# ESP32_BLDC_Motor_Driver.net
KiCad netlist of a schematic drawn in EAGLE
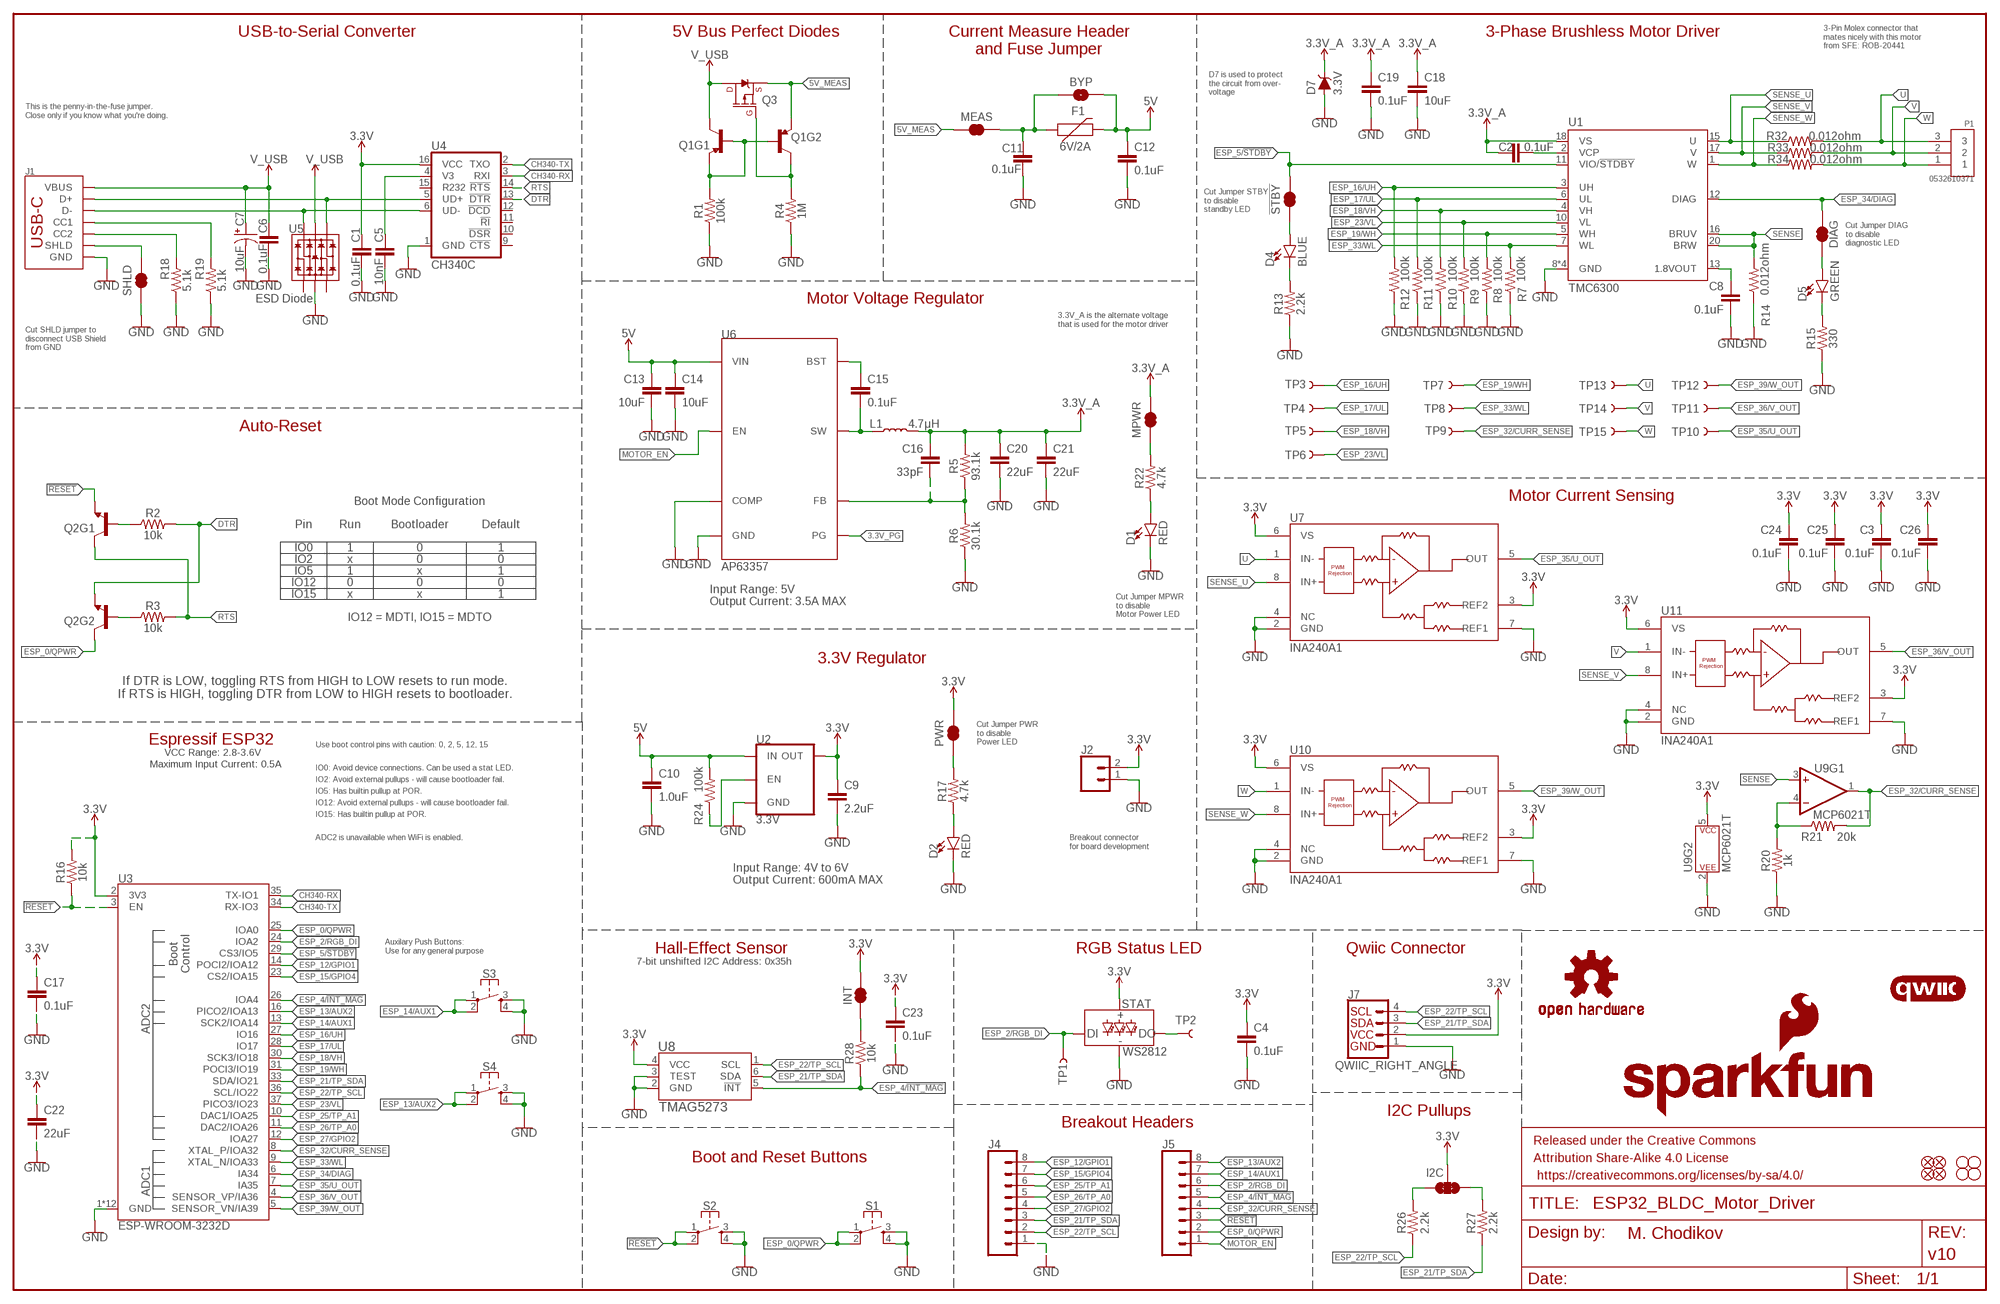
[diagram p0: schematic, sheet 1]

(export (version "E")
  (design (tool "Eeschema 10.0.6"))
  (components
    (comp (ref "!STBY")
      (value "JUMPER-SMT_2_NC_TRACE_SILK")
      (footprint "eagle-import:SMT-JUMPER_2_NC_TRACE_SILK")
      (fields (field (name "SPICEPREFIX") "B"))
      (libsource (lib "eagle-import") (part "JUMPER-SMT_2_NC_TRACE_SILK"))
    )
    (comp (ref "BYP")
      (value "JUMPER-SMT_2_NO_SILK")
      (footprint "eagle-import:SMT-JUMPER_2_NO_SILK")
      (libsource (lib "eagle-import") (part "JUMPER-SMT_2_NO_SILK"))
    )
    (comp (ref "C1")
      (value "0.1uF")
      (footprint "eagle-import:0603")
      (libsource (lib "eagle-import") (part "0.1UF-0603-25V-10%-X7R-WE"))
    )
    (comp (ref "C2")
      (value "0.1uF")
      (footprint "eagle-import:0603")
      (libsource (lib "eagle-import") (part "0.1UF-0603-25V-10%-X7R-WE"))
    )
    (comp (ref "C3")
      (value "0.1uF")
      (footprint "eagle-import:0603")
      (libsource (lib "eagle-import") (part "0.1UF-0603-25V-5%"))
    )
    (comp (ref "C4")
      (value "0.1uF")
      (footprint "eagle-import:0603")
      (libsource (lib "eagle-import") (part "0.1UF-0603-25V-10%-X7R-WE"))
    )
    (comp (ref "C5")
      (value "10nF")
      (footprint "eagle-import:0603")
      (libsource (lib "eagle-import") (part "10NF-0603-50V-10%"))
    )
    (comp (ref "C6")
      (value "0.1uF")
      (footprint "eagle-import:0603")
      (libsource (lib "eagle-import") (part "0.1UF-0603-25V-(+80/-20%)"))
    )
    (comp (ref "C7")
      (value "10uF")
      (footprint "eagle-import:0603-POLAR")
      (libsource (lib "eagle-import") (part "10UF-POLAR-0603-6.3V-20%(TANT)"))
    )
    (comp (ref "C8")
      (value "0.1uF")
      (footprint "eagle-import:0603")
      (libsource (lib "eagle-import") (part "0.1UF-0603-25V-10%-X7R-WE"))
    )
    (comp (ref "C9")
      (value "2.2uF")
      (footprint "eagle-import:0603")
      (libsource (lib "eagle-import") (part "2.2UF-0603-10V-20%"))
    )
    (comp (ref "C10")
      (value "1.0uF")
      (footprint "eagle-import:0603")
      (libsource (lib "eagle-import") (part "1.0UF-0603-16V-10%-X7R"))
    )
    (comp (ref "C11")
      (value "0.1uF")
      (footprint "eagle-import:0603")
      (libsource (lib "eagle-import") (part "0.1UF-0603-25V-(+80/-20%)"))
    )
    (comp (ref "C12")
      (value "0.1uF")
      (footprint "eagle-import:0603")
      (libsource (lib "eagle-import") (part "0.1UF-0603-25V-(+80/-20%)"))
    )
    (comp (ref "C13")
      (value "10uF")
      (footprint "eagle-import:0603")
      (libsource (lib "eagle-import") (part "10UF-0603-6.3V-20%"))
    )
    (comp (ref "C14")
      (value "10uF")
      (footprint "eagle-import:0603")
      (libsource (lib "eagle-import") (part "10UF-0603-6.3V-20%"))
    )
    (comp (ref "C15")
      (value "0.1uF")
      (footprint "eagle-import:0603")
      (libsource (lib "eagle-import") (part "0.1UF-0603-25V-5%"))
    )
    (comp (ref "C16")
      (value "33pF")
      (footprint "eagle-import:0603")
      (libsource (lib "eagle-import") (part "33PF-0603-50V-5%"))
    )
    (comp (ref "C17")
      (value "0.1uF")
      (footprint "eagle-import:0603")
      (libsource (lib "eagle-import") (part "0.1UF-0603-25V-5%"))
    )
    (comp (ref "C18")
      (value "10uF")
      (footprint "eagle-import:0603")
      (libsource (lib "eagle-import") (part "10UF-0603-6.3V-20%"))
    )
    (comp (ref "C19")
      (value "0.1uF")
      (footprint "eagle-import:0603")
      (libsource (lib "eagle-import") (part "0.1UF-0603-25V-10%-X7R-WE"))
    )
    (comp (ref "C20")
      (value "22uF")
      (footprint "eagle-import:0603")
      (libsource (lib "eagle-import") (part "22UF-0603-6.3V-20%"))
    )
    (comp (ref "C21")
      (value "22uF")
      (footprint "eagle-import:0603")
      (libsource (lib "eagle-import") (part "22UF-0603-6.3V-20%"))
    )
    (comp (ref "C22")
      (value "22uF")
      (footprint "eagle-import:0603")
      (libsource (lib "eagle-import") (part "22UF-0603-6.3V-20%"))
    )
    (comp (ref "C23")
      (value "0.1uF")
      (footprint "eagle-import:0402")
      (libsource (lib "eagle-import") (part "0.1UF-0402-10V-10%-X7R"))
    )
    (comp (ref "C24")
      (value "0.1uF")
      (footprint "eagle-import:0603")
      (libsource (lib "eagle-import") (part "0.1UF-0603-25V-5%"))
    )
    (comp (ref "C25")
      (value "0.1uF")
      (footprint "eagle-import:0603")
      (libsource (lib "eagle-import") (part "0.1UF-0603-25V-5%"))
    )
    (comp (ref "C26")
      (value "0.1uF")
      (footprint "eagle-import:0603")
      (libsource (lib "eagle-import") (part "0.1UF-0603-25V-5%"))
    )
    (comp (ref "D1")
      (value "RED")
      (footprint "eagle-import:LED-0603")
      (libsource (lib "eagle-import") (part "LED-RED_0603-KB"))
    )
    (comp (ref "D2")
      (value "RED")
      (footprint "eagle-import:LED-0603")
      (libsource (lib "eagle-import") (part "LED-RED_0603-KB"))
    )
    (comp (ref "D4")
      (value "BLUE")
      (footprint "eagle-import:LED-0603")
      (libsource (lib "eagle-import") (part "LED-BLUE0603"))
    )
    (comp (ref "D5")
      (value "GREEN")
      (footprint "eagle-import:LED-0603")
      (libsource (lib "eagle-import") (part "LED-GREEN0603"))
    )
    (comp (ref "D7")
      (value "3.3V")
      (footprint "eagle-import:SOD-323")
      (libsource (lib "eagle-import") (part "DIODE-ZENER-MM3Z3V3T1G"))
    )
    (comp (ref "DIAG")
      (value "JUMPER-SMT_2_NC_TRACE_SILK")
      (footprint "eagle-import:SMT-JUMPER_2_NC_TRACE_SILK")
      (libsource (lib "eagle-import") (part "JUMPER-SMT_2_NC_TRACE_SILK"))
    )
    (comp (ref "F1")
      (value "6V/2A")
      (footprint "eagle-import:1210")
      (libsource (lib "eagle-import") (part "PPTC_6V2A"))
    )
    (comp (ref "FD1")
      (value "FIDUCIALUFIDUCIAL")
      (footprint "eagle-import:FIDUCIAL-MICRO")
      (libsource (lib "eagle-import") (part "FIDUCIALUFIDUCIAL"))
    )
    (comp (ref "FD2")
      (value "FIDUCIALUFIDUCIAL")
      (footprint "eagle-import:FIDUCIAL-MICRO")
      (libsource (lib "eagle-import") (part "FIDUCIALUFIDUCIAL"))
    )
    (comp (ref "FD3")
      (value "FIDUCIALUFIDUCIAL")
      (footprint "eagle-import:FIDUCIAL-MICRO")
      (libsource (lib "eagle-import") (part "FIDUCIALUFIDUCIAL"))
    )
    (comp (ref "FD4")
      (value "FIDUCIALUFIDUCIAL")
      (footprint "eagle-import:FIDUCIAL-MICRO")
      (libsource (lib "eagle-import") (part "FIDUCIALUFIDUCIAL"))
    )
    (comp (ref "FRAME1")
      (value "FRAME-LEDGER")
      (footprint "eagle-import:CREATIVE_COMMONS")
      (fields (field (name "DESIGNER") "M. Chodikov") (field (name "REV") "v10"))
      (libsource (lib "eagle-import") (part "FRAME-LEDGER"))
    )
    (comp (ref "H1")
      (value "STAND-OFF")
      (footprint "eagle-import:STAND-OFF")
      (libsource (lib "eagle-import") (part "STAND-OFF"))
    )
    (comp (ref "H2")
      (value "STAND-OFF")
      (footprint "eagle-import:STAND-OFF")
      (libsource (lib "eagle-import") (part "STAND-OFF"))
    )
    (comp (ref "H3")
      (value "STAND-OFF")
      (footprint "eagle-import:STAND-OFF")
      (libsource (lib "eagle-import") (part "STAND-OFF"))
    )
    (comp (ref "H4")
      (value "STAND-OFF")
      (footprint "eagle-import:STAND-OFF")
      (libsource (lib "eagle-import") (part "STAND-OFF"))
    )
    (comp (ref "I2C")
      (value "JUMPER-SMT_3_2-NC_TRACE_SILK")
      (footprint "eagle-import:SMT-JUMPER_3_2-NC_TRACE_SILK")
      (libsource (lib "eagle-import") (part "JUMPER-SMT_3_2-NC_TRACE_SILK"))
    )
    (comp (ref "INT")
      (value "JUMPER-SMT_2_NC_TRACE_SILK")
      (footprint "eagle-import:SMT-JUMPER_2_NC_TRACE_SILK")
      (libsource (lib "eagle-import") (part "JUMPER-SMT_2_NC_TRACE_SILK"))
    )
    (comp (ref "J1")
      (value "USB-C Connector")
      (footprint "eagle-import:USB-C-16P_4LAYER-PADS")
      (libsource (lib "eagle-import") (part "USB_C_4-LAYER_PADS"))
    )
    (comp (ref "J2")
      (value "CONN_021X02_NO_SILK")
      (footprint "eagle-import:1X02_NO_SILK")
      (libsource (lib "eagle-import") (part "CONN_021X02_NO_SILK"))
    )
    (comp (ref "J4")
      (value "Breadboard Connector")
      (footprint "eagle-import:1X08_NO_SILK")
      (libsource (lib "eagle-import") (part "CONN_08NO_SILK_DNP"))
    )
    (comp (ref "J5")
      (value "Breadboard Headers")
      (footprint "eagle-import:1X08_NO_SILK")
      (libsource (lib "eagle-import") (part "CONN_08NO_SILK_DNP"))
    )
    (comp (ref "J7")
      (value "QWIIC_RIGHT_ANGLE")
      (footprint "eagle-import:JST04_1MM_RA")
      (libsource (lib "eagle-import") (part "QWIIC_CONNECTORJS-1MM"))
    )
    (comp (ref "L1")
      (value "4.7μH")
      (footprint "eagle-import:INDUCTOR_4X4MM")
      (libsource (lib "eagle-import") (part "4.7μH_SHIELDED_INDUCTORNPIS_LS"))
    )
    (comp (ref "LOGO1")
      (value "SFE_LOGO_NAMEBLANK")
      (footprint "eagle-import:BLANK")
      (libsource (lib "eagle-import") (part "SFE_LOGO_NAMEBLANK"))
    )
    (comp (ref "LOGO2")
      (value "OSHW-LOGOM")
      (footprint "eagle-import:OSHW-LOGO-M")
      (libsource (lib "eagle-import") (part "OSHW-LOGOM"))
    )
    (comp (ref "LOGO3")
      (value "SFE_LOGO_FLAME.2_INCH")
      (footprint "eagle-import:SFE_LOGO_FLAME_.2")
      (libsource (lib "eagle-import") (part "SFE_LOGO_FLAME.2_INCH"))
    )
    (comp (ref "LOGO4")
      (value "QWIIC_LOGO_5MM")
      (footprint "eagle-import:QWIIC_5MM")
      (libsource (lib "eagle-import") (part "QWIIC_LOGO_5MM"))
    )
    (comp (ref "MEAS")
      (value "JUMPER-COMBO_2_NC_TRACE")
      (footprint "eagle-import:COMBO-JUMPER_2_NC_TRACE")
      (libsource (lib "eagle-import") (part "JUMPER-COMBO_2_NC_TRACE"))
    )
    (comp (ref "MPWR")
      (value "JUMPER-SMT_2_NC_TRACE_SILK")
      (footprint "eagle-import:SMT-JUMPER_2_NC_TRACE_SILK")
      (libsource (lib "eagle-import") (part "JUMPER-SMT_2_NC_TRACE_SILK"))
    )
    (comp (ref "P1")
      (value "0532610371")
      (footprint "eagle-import:MOLEX_0532610371")
      (libsource (lib "eagle-import") (part "0532610371"))
    )
    (comp (ref "PWR")
      (value "JUMPER-SMT_2_NC_TRACE_SILK")
      (footprint "eagle-import:SMT-JUMPER_2_NC_TRACE_SILK")
      (libsource (lib "eagle-import") (part "JUMPER-SMT_2_NC_TRACE_SILK"))
    )
    (comp (ref "Q1")
      (value "TRANS_PNP_DUALSOT-363")
      (footprint "eagle-import:SOT363_PHILIPS")
      (libsource (lib "eagle-import") (part "TRANS_PNP_DUALSOT-363"))
    )
    (comp (ref "Q2")
      (value "NPN Transistors")
      (footprint "eagle-import:SC70-6")
      (libsource (lib "eagle-import") (part "TRANS_NPN_DUAL-MBT3904DW1T1"))
    )
    (comp (ref "Q3")
      (value "20V/4.2A/52mΩ/1.4W")
      (footprint "eagle-import:SOT23-3")
      (libsource (lib "eagle-import") (part "MOSFET_PCH-DMG2305UX-7"))
    )
    (comp (ref "R1")
      (value "100k")
      (footprint "eagle-import:0603")
      (libsource (lib "eagle-import") (part "100KOHM-0603-1/10W-1%"))
    )
    (comp (ref "R2")
      (value "10k")
      (footprint "eagle-import:0603")
      (libsource (lib "eagle-import") (part "10KOHM-0603-1/10W-1%"))
    )
    (comp (ref "R3")
      (value "10k")
      (footprint "eagle-import:0603")
      (libsource (lib "eagle-import") (part "10KOHM-0603-1/10W-1%"))
    )
    (comp (ref "R4")
      (value "1M")
      (footprint "eagle-import:0603")
      (libsource (lib "eagle-import") (part "1MOHM-0603-1/4W-5%"))
    )
    (comp (ref "R5")
      (value "93.1k")
      (footprint "eagle-import:0603")
      (libsource (lib "eagle-import") (part "93.1KOHM"))
    )
    (comp (ref "R6")
      (value "30.1k")
      (footprint "eagle-import:0603")
      (libsource (lib "eagle-import") (part "30.1KOHM-0603-1/10W-1%"))
    )
    (comp (ref "R7")
      (value "100k")
      (footprint "eagle-import:0603")
      (libsource (lib "eagle-import") (part "100KOHM-0603-1/10W-1%"))
    )
    (comp (ref "R8")
      (value "100k")
      (footprint "eagle-import:0603")
      (libsource (lib "eagle-import") (part "100KOHM-0603-1/10W-1%"))
    )
    (comp (ref "R9")
      (value "100k")
      (footprint "eagle-import:0603")
      (libsource (lib "eagle-import") (part "100KOHM-0603-1/10W-1%"))
    )
    (comp (ref "R10")
      (value "100k")
      (footprint "eagle-import:0603")
      (libsource (lib "eagle-import") (part "100KOHM-0603-1/10W-1%"))
    )
    (comp (ref "R11")
      (value "100k")
      (footprint "eagle-import:0603")
      (libsource (lib "eagle-import") (part "100KOHM-0603-1/10W-1%"))
    )
    (comp (ref "R12")
      (value "100k")
      (footprint "eagle-import:0603")
      (libsource (lib "eagle-import") (part "100KOHM-0603-1/10W-1%"))
    )
    (comp (ref "R13")
      (value "2.2k")
      (footprint "eagle-import:0603")
      (libsource (lib "eagle-import") (part "2.2KOHM-0603-1/10W-1%"))
    )
    (comp (ref "R14")
      (value "0.012ohm")
      (footprint "eagle-import:0603")
      (libsource (lib "eagle-import") (part "0.012OHM0603"))
    )
    (comp (ref "R15")
      (value "330")
      (footprint "eagle-import:0603")
      (libsource (lib "eagle-import") (part "330OHM-0603-1/10W-1%"))
    )
    (comp (ref "R16")
      (value "10k")
      (footprint "eagle-import:0603")
      (libsource (lib "eagle-import") (part "10KOHM-0603-1/10W-1%"))
    )
    (comp (ref "R17")
      (value "4.7k")
      (footprint "eagle-import:0603")
      (libsource (lib "eagle-import") (part "4.7KOHM-0603-1/10W-1%"))
    )
    (comp (ref "R18")
      (value "5.1k")
      (footprint "eagle-import:0603")
      (libsource (lib "eagle-import") (part "5.1KOHM5.1KOHM-0603-1/10W-1%"))
    )
    (comp (ref "R19")
      (value "5.1k")
      (footprint "eagle-import:0603")
      (libsource (lib "eagle-import") (part "5.1KOHM5.1KOHM-0603-1/10W-1%"))
    )
    (comp (ref "R20")
      (value "1k")
      (footprint "eagle-import:0603")
      (libsource (lib "eagle-import") (part "1KOHM-0603-1/10W-1%"))
    )
    (comp (ref "R21")
      (value "20k")
      (footprint "eagle-import:0603")
      (libsource (lib "eagle-import") (part "20KOHM-0603-1/10W-1%"))
    )
    (comp (ref "R22")
      (value "4.7k")
      (footprint "eagle-import:0603")
      (libsource (lib "eagle-import") (part "4.7KOHM-0603-1/10W-1%"))
    )
    (comp (ref "R24")
      (value "100k")
      (footprint "eagle-import:0603")
      (libsource (lib "eagle-import") (part "100KOHM-0603-1/10W-1%"))
    )
    (comp (ref "R26")
      (value "2.2k")
      (footprint "eagle-import:0603")
      (libsource (lib "eagle-import") (part "2.2KOHM-0603-1/10W-1%"))
    )
    (comp (ref "R27")
      (value "2.2k")
      (footprint "eagle-import:0603")
      (libsource (lib "eagle-import") (part "2.2KOHM-0603-1/10W-1%"))
    )
    (comp (ref "R28")
      (value "10k")
      (footprint "eagle-import:0603")
      (libsource (lib "eagle-import") (part "10KOHM-0603-1/10W-1%"))
    )
    (comp (ref "R32")
      (value "0.012ohm")
      (footprint "eagle-import:0603")
      (libsource (lib "eagle-import") (part "0.012OHM0603"))
    )
    (comp (ref "R33")
      (value "0.012ohm")
      (footprint "eagle-import:0603")
      (libsource (lib "eagle-import") (part "0.012OHM0603"))
    )
    (comp (ref "R34")
      (value "0.012ohm")
      (footprint "eagle-import:0603")
      (libsource (lib "eagle-import") (part "0.012OHM0603"))
    )
    (comp (ref "S1")
      (value "MOMENTARY-SWITCH-SPST-2-SMD-5.2MM-TALL")
      (footprint "eagle-import:TACTILE_SWITCH_SMD_5.2MM")
      (libsource (lib "eagle-import") (part "MOMENTARY-SWITCH-SPST-2-SMD-5.2MM-TALL"))
    )
    (comp (ref "S2")
      (value "MOMENTARY-SWITCH-SPST-2-SMD-5.2MM-TALL")
      (footprint "eagle-import:TACTILE_SWITCH_SMD_5.2MM")
      (libsource (lib "eagle-import") (part "MOMENTARY-SWITCH-SPST-2-SMD-5.2MM-TALL"))
    )
    (comp (ref "S3")
      (value "MOMENTARY-SWITCH-SPST-2-SMD-5.2MM-TALL")
      (footprint "eagle-import:TACTILE_SWITCH_SMD_5.2MM")
      (libsource (lib "eagle-import") (part "MOMENTARY-SWITCH-SPST-2-SMD-5.2MM-TALL"))
    )
    (comp (ref "S4")
      (value "MOMENTARY-SWITCH-SPST-2-SMD-5.2MM-TALL")
      (footprint "eagle-import:TACTILE_SWITCH_SMD_5.2MM")
      (libsource (lib "eagle-import") (part "MOMENTARY-SWITCH-SPST-2-SMD-5.2MM-TALL"))
    )
    (comp (ref "SHLD")
      (value "JUMPER-SMT_2_NC_TRACE_SILK")
      (footprint "eagle-import:SMT-JUMPER_2_NC_TRACE_SILK")
      (libsource (lib "eagle-import") (part "JUMPER-SMT_2_NC_TRACE_SILK"))
    )
    (comp (ref "STAT")
      (value "WS2812_2020")
      (footprint "eagle-import:WS2812-2020")
      (libsource (lib "eagle-import") (part "WS2812_2020"))
    )
    (comp (ref "TP1")
      (value "TEST-POINT3X4")
      (footprint "eagle-import:PAD.03X.04")
      (libsource (lib "eagle-import") (part "TEST-POINT3X4"))
    )
    (comp (ref "TP2")
      (value "TEST-POINT3X4")
      (footprint "eagle-import:PAD.03X.04")
      (libsource (lib "eagle-import") (part "TEST-POINT3X4"))
    )
    (comp (ref "TP3")
      (value "TEST-POINT3X4")
      (footprint "eagle-import:PAD.03X.04")
      (libsource (lib "eagle-import") (part "TEST-POINT3X4"))
    )
    (comp (ref "TP4")
      (value "TEST-POINT3X4")
      (footprint "eagle-import:PAD.03X.04")
      (libsource (lib "eagle-import") (part "TEST-POINT3X4"))
    )
    (comp (ref "TP5")
      (value "TEST-POINT3X4")
      (footprint "eagle-import:PAD.03X.04")
      (libsource (lib "eagle-import") (part "TEST-POINT3X4"))
    )
    (comp (ref "TP6")
      (value "TEST-POINT3X4")
      (footprint "eagle-import:PAD.03X.04")
      (libsource (lib "eagle-import") (part "TEST-POINT3X4"))
    )
    (comp (ref "TP7")
      (value "TEST-POINT3X4")
      (footprint "eagle-import:PAD.03X.04")
      (libsource (lib "eagle-import") (part "TEST-POINT3X4"))
    )
    (comp (ref "TP8")
      (value "TEST-POINT3X4")
      (footprint "eagle-import:PAD.03X.04")
      (libsource (lib "eagle-import") (part "TEST-POINT3X4"))
    )
    (comp (ref "TP9")
      (value "TEST-POINT3X4")
      (footprint "eagle-import:PAD.03X.04")
      (libsource (lib "eagle-import") (part "TEST-POINT3X4"))
    )
    (comp (ref "TP10")
      (value "TEST-POINT3X4")
      (footprint "eagle-import:PAD.03X.04")
      (libsource (lib "eagle-import") (part "TEST-POINT3X4"))
    )
    (comp (ref "TP11")
      (value "TEST-POINT3X4")
      (footprint "eagle-import:PAD.03X.04")
      (libsource (lib "eagle-import") (part "TEST-POINT3X4"))
    )
    (comp (ref "TP12")
      (value "TEST-POINT3X4")
      (footprint "eagle-import:PAD.03X.04")
      (libsource (lib "eagle-import") (part "TEST-POINT3X4"))
    )
    (comp (ref "TP13")
      (value "TEST-POINT3X4")
      (footprint "eagle-import:PAD.03X.04")
      (libsource (lib "eagle-import") (part "TEST-POINT3X4"))
    )
    (comp (ref "TP14")
      (value "TEST-POINT3X4")
      (footprint "eagle-import:PAD.03X.04")
      (libsource (lib "eagle-import") (part "TEST-POINT3X4"))
    )
    (comp (ref "TP15")
      (value "TEST-POINT3X4")
      (footprint "eagle-import:PAD.03X.04")
      (libsource (lib "eagle-import") (part "TEST-POINT3X4"))
    )
    (comp (ref "U1")
      (value "TMC6300")
      (footprint "eagle-import:QFN-20")
      (libsource (lib "eagle-import") (part "TMC6300"))
    )
    (comp (ref "U2")
      (value "3.3V")
      (footprint "eagle-import:SOT23-5")
      (libsource (lib "eagle-import") (part "V_REG_AP2112K-3.3V"))
    )
    (comp (ref "U3")
      (value "ESP-WROOM-3232D")
      (footprint "eagle-import:ESP-WROOM-32D")
      (libsource (lib "eagle-import") (part "ESP-WROOM-3232D"))
    )
    (comp (ref "U4")
      (value "CH340C")
      (footprint "eagle-import:SO016")
      (libsource (lib "eagle-import") (part "CH340C"))
    )
    (comp (ref "U5")
      (value "ESD Diode")
      (footprint "eagle-import:SOT-23-6")
      (libsource (lib "eagle-import") (part "TVS_DIODE_ARRAY_DT1042-04SO-7"))
    )
    (comp (ref "U6")
      (value "AP63357")
      (footprint "eagle-import:V-DFN3020-13")
      (libsource (lib "eagle-import") (part "AP63357"))
    )
    (comp (ref "U7")
      (value "INA240A1")
      (footprint "eagle-import:D8_TEX")
      (libsource (lib "eagle-import") (part "INA240A1D"))
    )
    (comp (ref "U8")
      (value "TMAG5273")
      (footprint "eagle-import:SOT23-6_DBV_TEX")
      (libsource (lib "eagle-import") (part "TMAG5273A1QDBVT"))
    )
    (comp (ref "U9")
      (value "MCP6021T")
      (footprint "eagle-import:SOT23-5")
      (libsource (lib "eagle-import") (part "MCP6021T-E/OT"))
    )
    (comp (ref "U10")
      (value "INA240A1")
      (footprint "eagle-import:D8_TEX")
      (libsource (lib "eagle-import") (part "INA240A1D"))
    )
    (comp (ref "U11")
      (value "INA240A1")
      (footprint "eagle-import:D8_TEX")
      (libsource (lib "eagle-import") (part "INA240A1D"))
    )
  )
  (nets
    (net (code "1") (name "/ESP_4{slash}~{INT_MAG}") (class "Default")
      (node (ref "J5") (pin "5") (pinfunction "5_5") (pintype "passive"))
      (node (ref "R28") (pin "1") (pinfunction "1_1") (pintype "passive"))
      (node (ref "U3") (pin "26") (pinfunction "IOA4_26") (pintype "bidirectional"))
      (node (ref "U8") (pin "5") (pinfunction "~{INT}_5") (pintype "bidirectional"))
    )
    (net (code "2") (name "/ESP_5{slash}~{STDBY}") (class "Default")
      (node (ref "!STBY") (pin "2") (pinfunction "2_2") (pintype "passive"))
      (node (ref "U1") (pin "11") (pinfunction "VIO/~{STDBY}_11") (pintype "bidirectional"))
      (node (ref "U3") (pin "29") (pinfunction "CS3/IO5_29") (pintype "bidirectional"))
    )
    (net (code "3") (name "/~{RESET}") (class "Default")
      (node (ref "J5") (pin "3") (pinfunction "3_3") (pintype "passive"))
      (node (ref "Q2") (pin "4") (pinfunction "E_4") (pintype "passive"))
      (node (ref "R16") (pin "1") (pinfunction "1_1") (pintype "passive"))
      (node (ref "S2") (pin "1") (pinfunction "1_1") (pintype "passive"))
      (node (ref "S2") (pin "2") (pinfunction "2_2") (pintype "passive"))
      (node (ref "U3") (pin "3") (pinfunction "EN_3") (pintype "bidirectional"))
    )
    (net (code "4") (name "3.3V") (class "Default")
      (node (ref "C1") (pin "1") (pinfunction "1_1") (pintype "passive"))
      (node (ref "C17") (pin "1") (pinfunction "1_1") (pintype "passive"))
      (node (ref "C22") (pin "1") (pinfunction "1_1") (pintype "passive"))
      (node (ref "C23") (pin "1") (pinfunction "1_1") (pintype "passive"))
      (node (ref "C24") (pin "1") (pinfunction "1_1") (pintype "passive"))
      (node (ref "C25") (pin "1") (pinfunction "1_1") (pintype "passive"))
      (node (ref "C26") (pin "1") (pinfunction "1_1") (pintype "passive"))
      (node (ref "C3") (pin "1") (pinfunction "1_1") (pintype "passive"))
      (node (ref "C4") (pin "1") (pinfunction "1_1") (pintype "passive"))
      (node (ref "C9") (pin "1") (pinfunction "1_1") (pintype "passive"))
      (node (ref "I2C") (pin "2") (pinfunction "2_2") (pintype "passive"))
      (node (ref "INT") (pin "2") (pinfunction "2_2") (pintype "passive"))
      (node (ref "J2") (pin "2") (pinfunction "2_2") (pintype "passive"))
      (node (ref "J7") (pin "2") (pinfunction "2_2") (pintype "power_in"))
      (node (ref "PWR") (pin "2") (pinfunction "2_2") (pintype "passive"))
      (node (ref "R16") (pin "2") (pinfunction "2_2") (pintype "passive"))
      (node (ref "STAT") (pin "VCC") (pinfunction "VCC_VCC") (pintype "bidirectional"))
      (node (ref "U10") (pin "3") (pinfunction "REF2_3") (pintype "input"))
      (node (ref "U10") (pin "6") (pinfunction "VS_6") (pintype "power_in"))
      (node (ref "U11") (pin "3") (pinfunction "REF2_3") (pintype "input"))
      (node (ref "U11") (pin "6") (pinfunction "VS_6") (pintype "power_in"))
      (node (ref "U2") (pin "5") (pinfunction "OUT_5") (pintype "passive"))
      (node (ref "U3") (pin "2") (pinfunction "3V3_2") (pintype "bidirectional"))
      (node (ref "U4") (pin "16") (pinfunction "VCC_16") (pintype "bidirectional"))
      (node (ref "U7") (pin "3") (pinfunction "REF2_3") (pintype "input"))
      (node (ref "U7") (pin "6") (pinfunction "VS_6") (pintype "power_in"))
      (node (ref "U8") (pin "4") (pinfunction "VCC_4") (pintype "power_in"))
      (node (ref "U9") (pin "5") (pinfunction "P$V+_5") (pintype "bidirectional"))
    )
    (net (code "5") (name "3.3V_A") (class "Default")
      (node (ref "C16") (pin "2") (pinfunction "2_2") (pintype "passive"))
      (node (ref "C18") (pin "1") (pinfunction "1_1") (pintype "passive"))
      (node (ref "C19") (pin "1") (pinfunction "1_1") (pintype "passive"))
      (node (ref "C2") (pin "1") (pinfunction "1_1") (pintype "passive"))
      (node (ref "C20") (pin "1") (pinfunction "1_1") (pintype "passive"))
      (node (ref "C21") (pin "1") (pinfunction "1_1") (pintype "passive"))
      (node (ref "D7") (pin "C") (pinfunction "C_C") (pintype "passive"))
      (node (ref "L1") (pin "P$2") (pinfunction "2_P$2") (pintype "passive"))
      (node (ref "MPWR") (pin "2") (pinfunction "2_2") (pintype "passive"))
      (node (ref "R5") (pin "2") (pinfunction "2_2") (pintype "passive"))
      (node (ref "U1") (pin "18") (pinfunction "VS_18") (pintype "bidirectional"))
    )
    (net (code "6") (name "3.3V_PG") (class "Default")
      (node (ref "U6") (pin "P$5") (pinfunction "PG_P$5") (pintype "output"))
    )
    (net (code "7") (name "5V") (class "Default")
      (node (ref "BYP") (pin "2") (pinfunction "2_2") (pintype "passive"))
      (node (ref "C10") (pin "1") (pinfunction "1_1") (pintype "passive"))
      (node (ref "C12") (pin "1") (pinfunction "1_1") (pintype "passive"))
      (node (ref "C13") (pin "1") (pinfunction "1_1") (pintype "passive"))
      (node (ref "C14") (pin "1") (pinfunction "1_1") (pintype "passive"))
      (node (ref "F1") (pin "2") (pinfunction "2_2") (pintype "bidirectional"))
      (node (ref "R24") (pin "2") (pinfunction "2_2") (pintype "passive"))
      (node (ref "U2") (pin "1") (pinfunction "IN_1") (pintype "input"))
      (node (ref "U6") (pin "P$1") (pinfunction "VIN_P$1") (pintype "power_in"))
    )
    (net (code "8") (name "5V_MEAS") (class "Default")
      (node (ref "MEAS") (pin "1") (pinfunction "1_1") (pintype "passive"))
      (node (ref "MEAS") (pin "3") (pinfunction "1_3") (pintype "passive"))
      (node (ref "Q1") (pin "4") (pinfunction "E_4") (pintype "passive"))
      (node (ref "Q3") (pin "2") (pinfunction "S_2") (pintype "bidirectional"))
    )
    (net (code "9") (name "CH340-RX") (class "Default")
      (node (ref "U3") (pin "35") (pinfunction "TX-IO1_35") (pintype "bidirectional"))
      (node (ref "U4") (pin "3") (pinfunction "RXI_3") (pintype "bidirectional"))
    )
    (net (code "10") (name "CH340-TX") (class "Default")
      (node (ref "U3") (pin "34") (pinfunction "RX-IO3_34") (pintype "bidirectional"))
      (node (ref "U4") (pin "2") (pinfunction "TXO_2") (pintype "bidirectional"))
    )
    (net (code "11") (name "DTR") (class "Default")
      (node (ref "Q2") (pin "1") (pinfunction "E_1") (pintype "passive"))
      (node (ref "R2") (pin "2") (pinfunction "2_2") (pintype "passive"))
      (node (ref "U4") (pin "13") (pinfunction "~{DTR}_13") (pintype "bidirectional"))
    )
    (net (code "12") (name "ESP_0{slash}QPWR") (class "Default")
      (node (ref "J5") (pin "2") (pinfunction "2_2") (pintype "passive"))
      (node (ref "Q2") (pin "6") (pinfunction "C_6") (pintype "passive"))
      (node (ref "S1") (pin "1") (pinfunction "1_1") (pintype "passive"))
      (node (ref "S1") (pin "2") (pinfunction "2_2") (pintype "passive"))
      (node (ref "U3") (pin "25") (pinfunction "IOA0_25") (pintype "bidirectional"))
    )
    (net (code "13") (name "ESP_2{slash}RGB_DI") (class "Default")
      (node (ref "J5") (pin "6") (pinfunction "6_6") (pintype "passive"))
      (node (ref "STAT") (pin "DI") (pinfunction "DI_DI") (pintype "bidirectional"))
      (node (ref "TP1") (pin "1") (pinfunction "1_1") (pintype "bidirectional"))
      (node (ref "U3") (pin "24") (pinfunction "IOA2_24") (pintype "bidirectional"))
    )
    (net (code "14") (name "ESP_12{slash}GPIO1") (class "Default")
      (node (ref "J4") (pin "8") (pinfunction "8_8") (pintype "passive"))
      (node (ref "U3") (pin "14") (pinfunction "POCI2/IOA12_14") (pintype "bidirectional"))
    )
    (net (code "15") (name "ESP_13{slash}AUX2") (class "Default")
      (node (ref "J5") (pin "8") (pinfunction "8_8") (pintype "passive"))
      (node (ref "S4") (pin "1") (pinfunction "1_1") (pintype "passive"))
      (node (ref "S4") (pin "2") (pinfunction "2_2") (pintype "passive"))
      (node (ref "U3") (pin "16") (pinfunction "PICO2/IOA13_16") (pintype "bidirectional"))
    )
    (net (code "16") (name "ESP_14{slash}AUX1") (class "Default")
      (node (ref "J5") (pin "7") (pinfunction "7_7") (pintype "passive"))
      (node (ref "S3") (pin "1") (pinfunction "1_1") (pintype "passive"))
      (node (ref "S3") (pin "2") (pinfunction "2_2") (pintype "passive"))
      (node (ref "U3") (pin "13") (pinfunction "SCK2/IOA14_13") (pintype "bidirectional"))
    )
    (net (code "17") (name "ESP_15{slash}GPIO4") (class "Default")
      (node (ref "J4") (pin "7") (pinfunction "7_7") (pintype "passive"))
      (node (ref "U3") (pin "23") (pinfunction "CS2/IOA15_23") (pintype "bidirectional"))
    )
    (net (code "18") (name "ESP_16{slash}UH") (class "Default")
      (node (ref "R12") (pin "2") (pinfunction "2_2") (pintype "passive"))
      (node (ref "TP3") (pin "1") (pinfunction "1_1") (pintype "bidirectional"))
      (node (ref "U1") (pin "3") (pinfunction "UH_3") (pintype "bidirectional"))
      (node (ref "U3") (pin "27") (pinfunction "IO16_27") (pintype "bidirectional"))
    )
    (net (code "19") (name "ESP_17{slash}UL") (class "Default")
      (node (ref "R11") (pin "2") (pinfunction "2_2") (pintype "passive"))
      (node (ref "TP4") (pin "1") (pinfunction "1_1") (pintype "bidirectional"))
      (node (ref "U1") (pin "6") (pinfunction "UL_6") (pintype "bidirectional"))
      (node (ref "U3") (pin "28") (pinfunction "IO17_28") (pintype "bidirectional"))
    )
    (net (code "20") (name "ESP_18{slash}VH") (class "Default")
      (node (ref "R10") (pin "2") (pinfunction "2_2") (pintype "passive"))
      (node (ref "TP5") (pin "1") (pinfunction "1_1") (pintype "bidirectional"))
      (node (ref "U1") (pin "4") (pinfunction "VH_4") (pintype "bidirectional"))
      (node (ref "U3") (pin "30") (pinfunction "SCK3/IO18_30") (pintype "bidirectional"))
    )
    (net (code "21") (name "ESP_19{slash}WH") (class "Default")
      (node (ref "R8") (pin "2") (pinfunction "2_2") (pintype "passive"))
      (node (ref "TP7") (pin "1") (pinfunction "1_1") (pintype "bidirectional"))
      (node (ref "U1") (pin "5") (pinfunction "WH_5") (pintype "bidirectional"))
      (node (ref "U3") (pin "31") (pinfunction "POCI3/IO19_31") (pintype "bidirectional"))
    )
    (net (code "22") (name "ESP_21{slash}TP_SDA") (class "Default")
      (node (ref "J4") (pin "3") (pinfunction "3_3") (pintype "passive"))
      (node (ref "J7") (pin "3") (pinfunction "3_3") (pintype "passive"))
      (node (ref "R27") (pin "1") (pinfunction "1_1") (pintype "passive"))
      (node (ref "U3") (pin "33") (pinfunction "SDA/IO21_33") (pintype "bidirectional"))
      (node (ref "U8") (pin "6") (pinfunction "SDA_6") (pintype "bidirectional"))
    )
    (net (code "23") (name "ESP_22{slash}TP_SCL") (class "Default")
      (node (ref "J4") (pin "2") (pinfunction "2_2") (pintype "passive"))
      (node (ref "J7") (pin "4") (pinfunction "4_4") (pintype "passive"))
      (node (ref "R26") (pin "1") (pinfunction "1_1") (pintype "passive"))
      (node (ref "U3") (pin "36") (pinfunction "SCL/IO22_36") (pintype "bidirectional"))
      (node (ref "U8") (pin "1") (pinfunction "SCL_1") (pintype "bidirectional"))
    )
    (net (code "24") (name "ESP_23{slash}VL") (class "Default")
      (node (ref "R9") (pin "2") (pinfunction "2_2") (pintype "passive"))
      (node (ref "TP6") (pin "1") (pinfunction "1_1") (pintype "bidirectional"))
      (node (ref "U1") (pin "10") (pinfunction "VL_10") (pintype "bidirectional"))
      (node (ref "U3") (pin "37") (pinfunction "PICO3/IO23_37") (pintype "bidirectional"))
    )
    (net (code "25") (name "ESP_25{slash}TP_A1") (class "Default")
      (node (ref "J4") (pin "6") (pinfunction "6_6") (pintype "passive"))
      (node (ref "U3") (pin "10") (pinfunction "DAC1/IOA25_10") (pintype "bidirectional"))
    )
    (net (code "26") (name "ESP_26{slash}TP_A0") (class "Default")
      (node (ref "J4") (pin "5") (pinfunction "5_5") (pintype "passive"))
      (node (ref "U3") (pin "11") (pinfunction "DAC2/IOA26_11") (pintype "bidirectional"))
    )
    (net (code "27") (name "ESP_27{slash}GPIO2") (class "Default")
      (node (ref "J4") (pin "4") (pinfunction "4_4") (pintype "passive"))
      (node (ref "U3") (pin "12") (pinfunction "IOA27_12") (pintype "bidirectional"))
    )
    (net (code "28") (name "ESP_32{slash}CURR_SENSE") (class "Default")
      (node (ref "J5") (pin "4") (pinfunction "4_4") (pintype "passive"))
      (node (ref "R21") (pin "2") (pinfunction "2_2") (pintype "passive"))
      (node (ref "TP9") (pin "1") (pinfunction "1_1") (pintype "bidirectional"))
      (node (ref "U3") (pin "8") (pinfunction "XTAL_P/IOA32_8") (pintype "bidirectional"))
      (node (ref "U9") (pin "1") (pinfunction "OUT_1") (pintype "output"))
    )
    (net (code "29") (name "ESP_33{slash}WL") (class "Default")
      (node (ref "R7") (pin "2") (pinfunction "2_2") (pintype "passive"))
      (node (ref "TP8") (pin "1") (pinfunction "1_1") (pintype "bidirectional"))
      (node (ref "U1") (pin "7") (pinfunction "WL_7") (pintype "bidirectional"))
      (node (ref "U3") (pin "9") (pinfunction "XTAL_N/IOA33_9") (pintype "bidirectional"))
    )
    (net (code "30") (name "ESP_34{slash}DIAG") (class "Default")
      (node (ref "DIAG") (pin "2") (pinfunction "2_2") (pintype "passive"))
      (node (ref "U1") (pin "12") (pinfunction "DIAG_12") (pintype "bidirectional"))
      (node (ref "U3") (pin "6") (pinfunction "IA34_6") (pintype "bidirectional"))
    )
    (net (code "31") (name "ESP_35{slash}U_OUT") (class "Default")
      (node (ref "TP10") (pin "1") (pinfunction "1_1") (pintype "bidirectional"))
      (node (ref "U3") (pin "7") (pinfunction "IA35_7") (pintype "bidirectional"))
      (node (ref "U7") (pin "5") (pinfunction "OUT_5") (pintype "output"))
    )
    (net (code "32") (name "ESP_36{slash}V_OUT") (class "Default")
      (node (ref "TP11") (pin "1") (pinfunction "1_1") (pintype "bidirectional"))
      (node (ref "U11") (pin "5") (pinfunction "OUT_5") (pintype "output"))
      (node (ref "U3") (pin "4") (pinfunction "SENSOR_VP/IA36_4") (pintype "bidirectional"))
    )
    (net (code "33") (name "ESP_39{slash}W_OUT") (class "Default")
      (node (ref "TP12") (pin "1") (pinfunction "1_1") (pintype "bidirectional"))
      (node (ref "U10") (pin "5") (pinfunction "OUT_5") (pintype "output"))
      (node (ref "U3") (pin "5") (pinfunction "SENSOR_VN/IA39_5") (pintype "bidirectional"))
    )
    (net (code "34") (name "GND") (class "Default")
      (node (ref "C1") (pin "2") (pinfunction "2_2") (pintype "passive"))
      (node (ref "C10") (pin "2") (pinfunction "2_2") (pintype "passive"))
      (node (ref "C11") (pin "2") (pinfunction "2_2") (pintype "passive"))
      (node (ref "C12") (pin "2") (pinfunction "2_2") (pintype "passive"))
      (node (ref "C13") (pin "2") (pinfunction "2_2") (pintype "passive"))
      (node (ref "C14") (pin "2") (pinfunction "2_2") (pintype "passive"))
      (node (ref "C17") (pin "2") (pinfunction "2_2") (pintype "passive"))
      (node (ref "C18") (pin "2") (pinfunction "2_2") (pintype "passive"))
      (node (ref "C19") (pin "2") (pinfunction "2_2") (pintype "passive"))
      (node (ref "C20") (pin "2") (pinfunction "2_2") (pintype "passive"))
      (node (ref "C21") (pin "2") (pinfunction "2_2") (pintype "passive"))
      (node (ref "C22") (pin "2") (pinfunction "2_2") (pintype "passive"))
      (node (ref "C23") (pin "2") (pinfunction "2_2") (pintype "passive"))
      (node (ref "C24") (pin "2") (pinfunction "2_2") (pintype "passive"))
      (node (ref "C25") (pin "2") (pinfunction "2_2") (pintype "passive"))
      (node (ref "C26") (pin "2") (pinfunction "2_2") (pintype "passive"))
      (node (ref "C3") (pin "2") (pinfunction "2_2") (pintype "passive"))
      (node (ref "C4") (pin "2") (pinfunction "2_2") (pintype "passive"))
      (node (ref "C5") (pin "2") (pinfunction "2_2") (pintype "passive"))
      (node (ref "C6") (pin "2") (pinfunction "2_2") (pintype "passive"))
      (node (ref "C7") (pin "-") (pinfunction "-_-") (pintype "passive"))
      (node (ref "C8") (pin "2") (pinfunction "2_2") (pintype "passive"))
      (node (ref "C9") (pin "2") (pinfunction "2_2") (pintype "passive"))
      (node (ref "D1") (pin "C") (pinfunction "C_C") (pintype "passive"))
      (node (ref "D2") (pin "C") (pinfunction "C_C") (pintype "passive"))
      (node (ref "D7") (pin "A") (pinfunction "A_A") (pintype "passive"))
      (node (ref "J1") (pin "GND") (pinfunction "GND_GND") (pintype "bidirectional"))
      (node (ref "J1") (pin "GND2") (pinfunction "GND_GND2") (pintype "bidirectional"))
      (node (ref "J2") (pin "1") (pinfunction "1_1") (pintype "passive"))
      (node (ref "J4") (pin "1") (pinfunction "1_1") (pintype "passive"))
      (node (ref "J7") (pin "1") (pinfunction "1_1") (pintype "power_in"))
      (node (ref "R1") (pin "1") (pinfunction "1_1") (pintype "passive"))
      (node (ref "R10") (pin "1") (pinfunction "1_1") (pintype "passive"))
      (node (ref "R11") (pin "1") (pinfunction "1_1") (pintype "passive"))
      (node (ref "R12") (pin "1") (pinfunction "1_1") (pintype "passive"))
      (node (ref "R13") (pin "1") (pinfunction "1_1") (pintype "passive"))
      (node (ref "R14") (pin "1") (pinfunction "1_1") (pintype "passive"))
      (node (ref "R15") (pin "1") (pinfunction "1_1") (pintype "passive"))
      (node (ref "R18") (pin "1") (pinfunction "1_1") (pintype "passive"))
      (node (ref "R19") (pin "1") (pinfunction "1_1") (pintype "passive"))
      (node (ref "R20") (pin "1") (pinfunction "1_1") (pintype "passive"))
      (node (ref "R4") (pin "1") (pinfunction "1_1") (pintype "passive"))
      (node (ref "R6") (pin "1") (pinfunction "1_1") (pintype "passive"))
      (node (ref "R7") (pin "1") (pinfunction "1_1") (pintype "passive"))
      (node (ref "R8") (pin "1") (pinfunction "1_1") (pintype "passive"))
      (node (ref "R9") (pin "1") (pinfunction "1_1") (pintype "passive"))
      (node (ref "S1") (pin "3") (pinfunction "3_3") (pintype "passive"))
      (node (ref "S1") (pin "4") (pinfunction "4_4") (pintype "passive"))
      (node (ref "S2") (pin "3") (pinfunction "3_3") (pintype "passive"))
      (node (ref "S2") (pin "4") (pinfunction "4_4") (pintype "passive"))
      (node (ref "S3") (pin "3") (pinfunction "3_3") (pintype "passive"))
      (node (ref "S3") (pin "4") (pinfunction "4_4") (pintype "passive"))
      (node (ref "S4") (pin "3") (pinfunction "3_3") (pintype "passive"))
      (node (ref "S4") (pin "4") (pinfunction "4_4") (pintype "passive"))
      (node (ref "SHLD") (pin "1") (pinfunction "1_1") (pintype "passive"))
      (node (ref "STAT") (pin "GND") (pinfunction "GND_GND") (pintype "bidirectional"))
      (node (ref "U1") (pin "14") (pinfunction "GND_14") (pintype "bidirectional"))
      (node (ref "U1") (pin "8") (pinfunction "GND_8") (pintype "bidirectional"))
      (node (ref "U1") (pin "9") (pinfunction "GND_9") (pintype "bidirectional"))
      (node (ref "U1") (pin "PAD") (pinfunction "GND_PAD") (pintype "bidirectional"))
      (node (ref "U10") (pin "2") (pinfunction "GND_2") (pintype "power_in"))
      (node (ref "U10") (pin "4") (pinfunction "NC_4") (pintype "power_in"))
      (node (ref "U10") (pin "7") (pinfunction "REF1_7") (pintype "input"))
      (node (ref "U11") (pin "2") (pinfunction "GND_2") (pintype "power_in"))
      (node (ref "U11") (pin "4") (pinfunction "NC_4") (pintype "power_in"))
      (node (ref "U11") (pin "7") (pinfunction "REF1_7") (pintype "input"))
      (node (ref "U2") (pin "2") (pinfunction "GND_2") (pintype "input"))
      (node (ref "U3") (pin "1") (pinfunction "GND_1") (pintype "bidirectional"))
      (node (ref "U3") (pin "15") (pinfunction "GND_15") (pintype "bidirectional"))
      (node (ref "U3") (pin "38") (pinfunction "GND_38") (pintype "bidirectional"))
      (node (ref "U3") (pin "GND") (pinfunction "GND_GND") (pintype "bidirectional"))
      (node (ref "U3") (pin "GNDT1") (pinfunction "GND_GNDT1") (pintype "bidirectional"))
      (node (ref "U3") (pin "GNDT2") (pinfunction "GND_GNDT2") (pintype "bidirectional"))
      (node (ref "U3") (pin "GNDT3") (pinfunction "GND_GNDT3") (pintype "bidirectional"))
      (node (ref "U3") (pin "GNDT4") (pinfunction "GND_GNDT4") (pintype "bidirectional"))
      (node (ref "U3") (pin "GNDT5") (pinfunction "GND_GNDT5") (pintype "bidirectional"))
      (node (ref "U3") (pin "GNDT6") (pinfunction "GND_GNDT6") (pintype "bidirectional"))
      (node (ref "U3") (pin "GNDT7") (pinfunction "GND_GNDT7") (pintype "bidirectional"))
      (node (ref "U3") (pin "GNDT8") (pinfunction "GND_GNDT8") (pintype "bidirectional"))
      (node (ref "U4") (pin "1") (pinfunction "GND_1") (pintype "bidirectional"))
      (node (ref "U5") (pin "2") (pinfunction "VSS_2") (pintype "bidirectional"))
      (node (ref "U6") (pin "P$4") (pinfunction "COMP_P$4") (pintype "bidirectional"))
      (node (ref "U6") (pin "P$8") (pinfunction "GND_P$8") (pintype "power_in"))
      (node (ref "U7") (pin "2") (pinfunction "GND_2") (pintype "power_in"))
      (node (ref "U7") (pin "4") (pinfunction "NC_4") (pintype "power_in"))
      (node (ref "U7") (pin "7") (pinfunction "REF1_7") (pintype "input"))
      (node (ref "U8") (pin "2") (pinfunction "GND_2") (pintype "passive"))
      (node (ref "U8") (pin "3") (pinfunction "TEST_3") (pintype "input"))
      (node (ref "U9") (pin "2") (pinfunction "P$V-_2") (pintype "bidirectional"))
    )
    (net (code "35") (name "MOTOR_EN") (class "Default")
      (node (ref "J5") (pin "1") (pinfunction "1_1") (pintype "passive"))
      (node (ref "U6") (pin "P$2") (pinfunction "EN_P$2") (pintype "bidirectional"))
    )
    (net (code "36") (name "Net-(!STBY-Pad1)") (class "Default")
      (node (ref "!STBY") (pin "1") (pinfunction "1_1") (pintype "passive"))
      (node (ref "D4") (pin "A") (pinfunction "A_A") (pintype "passive"))
    )
    (net (code "37") (name "Net-(BYP-Pad1)") (class "Default")
      (node (ref "BYP") (pin "1") (pinfunction "1_1") (pintype "passive"))
      (node (ref "C11") (pin "1") (pinfunction "1_1") (pintype "passive"))
      (node (ref "F1") (pin "1") (pinfunction "1_1") (pintype "bidirectional"))
      (node (ref "MEAS") (pin "2") (pinfunction "2_2") (pintype "passive"))
      (node (ref "MEAS") (pin "4") (pinfunction "2_4") (pintype "passive"))
    )
    (net (code "38") (name "Net-(D1-PadA)") (class "Default")
      (node (ref "D1") (pin "A") (pinfunction "A_A") (pintype "passive"))
      (node (ref "R22") (pin "1") (pinfunction "1_1") (pintype "passive"))
    )
    (net (code "39") (name "Net-(D2-PadA)") (class "Default")
      (node (ref "D2") (pin "A") (pinfunction "A_A") (pintype "passive"))
      (node (ref "R17") (pin "1") (pinfunction "1_1") (pintype "passive"))
    )
    (net (code "40") (name "Net-(D4-PadC)") (class "Default")
      (node (ref "D4") (pin "C") (pinfunction "C_C") (pintype "passive"))
      (node (ref "R13") (pin "2") (pinfunction "2_2") (pintype "passive"))
    )
    (net (code "41") (name "Net-(D5-PadA)") (class "Default")
      (node (ref "D5") (pin "A") (pinfunction "A_A") (pintype "passive"))
      (node (ref "DIAG") (pin "1") (pinfunction "1_1") (pintype "passive"))
    )
    (net (code "42") (name "Net-(D5-PadC)") (class "Default")
      (node (ref "D5") (pin "C") (pinfunction "C_C") (pintype "passive"))
      (node (ref "R15") (pin "2") (pinfunction "2_2") (pintype "passive"))
    )
    (net (code "43") (name "Net-(I2C-Pad1)") (class "Default")
      (node (ref "I2C") (pin "1") (pinfunction "1_1") (pintype "passive"))
      (node (ref "R27") (pin "2") (pinfunction "2_2") (pintype "passive"))
    )
    (net (code "44") (name "Net-(I2C-Pad3)") (class "Default")
      (node (ref "I2C") (pin "3") (pinfunction "3_3") (pintype "passive"))
      (node (ref "R26") (pin "2") (pinfunction "2_2") (pintype "passive"))
    )
    (net (code "45") (name "Net-(INT-Pad1)") (class "Default")
      (node (ref "INT") (pin "1") (pinfunction "1_1") (pintype "passive"))
      (node (ref "R28") (pin "2") (pinfunction "2_2") (pintype "passive"))
    )
    (net (code "46") (name "Net-(J1-CC1)") (class "Default")
      (node (ref "J1") (pin "A5") (pinfunction "CC1_A5") (pintype "bidirectional"))
      (node (ref "R19") (pin "2") (pinfunction "2_2") (pintype "passive"))
    )
    (net (code "47") (name "Net-(J1-CC2)") (class "Default")
      (node (ref "J1") (pin "B5") (pinfunction "CC2_B5") (pintype "bidirectional"))
      (node (ref "R18") (pin "2") (pinfunction "2_2") (pintype "passive"))
    )
    (net (code "48") (name "Net-(J1-SHLD-PadSHLD1)") (class "Default")
      (node (ref "J1") (pin "SHLD1") (pinfunction "SHLD_SHLD1") (pintype "bidirectional"))
      (node (ref "J1") (pin "SHLD2") (pinfunction "SHLD_SHLD2") (pintype "bidirectional"))
      (node (ref "J1") (pin "SHLD3") (pinfunction "SHLD_SHLD3") (pintype "bidirectional"))
      (node (ref "J1") (pin "SHLD4") (pinfunction "SHLD_SHLD4") (pintype "bidirectional"))
      (node (ref "SHLD") (pin "2") (pinfunction "2_2") (pintype "passive"))
    )
    (net (code "49") (name "Net-(L1-1)") (class "Default")
      (node (ref "C15") (pin "2") (pinfunction "2_2") (pintype "passive"))
      (node (ref "L1") (pin "P$1") (pinfunction "1_P$1") (pintype "passive"))
      (node (ref "U6") (pin "P$7") (pinfunction "SW_P$7") (pintype "power_in"))
      (node (ref "U6") (pin "P$9") (pinfunction "SW_P$9") (pintype "power_in"))
    )
    (net (code "50") (name "Net-(MPWR-Pad1)") (class "Default")
      (node (ref "MPWR") (pin "1") (pinfunction "1_1") (pintype "passive"))
      (node (ref "R22") (pin "2") (pinfunction "2_2") (pintype "passive"))
    )
    (net (code "51") (name "Net-(PWR-Pad1)") (class "Default")
      (node (ref "PWR") (pin "1") (pinfunction "1_1") (pintype "passive"))
      (node (ref "R17") (pin "2") (pinfunction "2_2") (pintype "passive"))
    )
    (net (code "52") (name "Net-(Q1A-B)") (class "Default")
      (node (ref "Q1") (pin "1") (pinfunction "E_1") (pintype "passive"))
      (node (ref "Q1") (pin "2") (pinfunction "B_2") (pintype "passive"))
      (node (ref "Q1") (pin "5") (pinfunction "B_5") (pintype "passive"))
      (node (ref "R1") (pin "2") (pinfunction "2_2") (pintype "passive"))
    )
    (net (code "53") (name "Net-(Q1B-C)") (class "Default")
      (node (ref "Q1") (pin "3") (pinfunction "C_3") (pintype "passive"))
      (node (ref "Q3") (pin "1") (pinfunction "G_1") (pintype "bidirectional"))
      (node (ref "R4") (pin "2") (pinfunction "2_2") (pintype "passive"))
    )
    (net (code "54") (name "Net-(Q2A-B)") (class "Default")
      (node (ref "Q2") (pin "5") (pinfunction "B_5") (pintype "passive"))
      (node (ref "R2") (pin "1") (pinfunction "1_1") (pintype "passive"))
    )
    (net (code "55") (name "Net-(Q2B-B)") (class "Default")
      (node (ref "Q2") (pin "2") (pinfunction "B_2") (pintype "passive"))
      (node (ref "R3") (pin "1") (pinfunction "1_1") (pintype "passive"))
    )
    (net (code "56") (name "Net-(STAT-PadDO)") (class "Default")
      (node (ref "STAT") (pin "DO") (pinfunction "DO_DO") (pintype "bidirectional"))
      (node (ref "TP2") (pin "1") (pinfunction "1_1") (pintype "bidirectional"))
    )
    (net (code "57") (name "Net-(U1-1.8VOUT)") (class "Default")
      (node (ref "C8") (pin "1") (pinfunction "1_1") (pintype "passive"))
      (node (ref "U1") (pin "13") (pinfunction "1.8VOUT_13") (pintype "bidirectional"))
    )
    (net (code "58") (name "Net-(U1-VCP)") (class "Default")
      (node (ref "C2") (pin "2") (pinfunction "2_2") (pintype "passive"))
      (node (ref "U1") (pin "2") (pinfunction "VCP_2") (pintype "bidirectional"))
    )
    (net (code "59") (name "Net-(U2-EN)") (class "Default")
      (node (ref "R24") (pin "1") (pinfunction "1_1") (pintype "passive"))
      (node (ref "U2") (pin "3") (pinfunction "EN_3") (pintype "input"))
    )
    (net (code "60") (name "Net-(U4-UD+)") (class "Default")
      (node (ref "J1") (pin "A6") (pinfunction "D+_A6") (pintype "bidirectional"))
      (node (ref "J1") (pin "B6") (pinfunction "D+_B6") (pintype "bidirectional"))
      (node (ref "U4") (pin "5") (pinfunction "UD+_5") (pintype "bidirectional"))
      (node (ref "U5") (pin "4") (pinfunction "IO3_4") (pintype "bidirectional"))
    )
    (net (code "61") (name "Net-(U4-UD-)") (class "Default")
      (node (ref "J1") (pin "A7") (pinfunction "D-_A7") (pintype "bidirectional"))
      (node (ref "J1") (pin "B7") (pinfunction "D-_B7") (pintype "bidirectional"))
      (node (ref "U4") (pin "6") (pinfunction "UD-_6") (pintype "bidirectional"))
      (node (ref "U5") (pin "6") (pinfunction "IO4_6") (pintype "bidirectional"))
    )
    (net (code "62") (name "Net-(U4-V3)") (class "Default")
      (node (ref "C5") (pin "1") (pinfunction "1_1") (pintype "passive"))
      (node (ref "U4") (pin "4") (pinfunction "V3_4") (pintype "bidirectional"))
    )
    (net (code "63") (name "Net-(U6-BST)") (class "Default")
      (node (ref "C15") (pin "1") (pinfunction "1_1") (pintype "passive"))
      (node (ref "U6") (pin "P$6") (pinfunction "BST_P$6") (pintype "bidirectional"))
    )
    (net (code "64") (name "Net-(U6-FB)") (class "Default")
      (node (ref "C16") (pin "1") (pinfunction "1_1") (pintype "passive"))
      (node (ref "R5") (pin "1") (pinfunction "1_1") (pintype "passive"))
      (node (ref "R6") (pin "2") (pinfunction "2_2") (pintype "passive"))
      (node (ref "U6") (pin "P$3") (pinfunction "FB_P$3") (pintype "input"))
    )
    (net (code "65") (name "Net-(U9A--IN)") (class "Default")
      (node (ref "R20") (pin "2") (pinfunction "2_2") (pintype "passive"))
      (node (ref "R21") (pin "1") (pinfunction "1_1") (pintype "passive"))
      (node (ref "U9") (pin "4") (pinfunction "-IN_4") (pintype "input"))
    )
    (net (code "66") (name "RTS") (class "Default")
      (node (ref "Q2") (pin "3") (pinfunction "C_3") (pintype "passive"))
      (node (ref "R3") (pin "2") (pinfunction "2_2") (pintype "passive"))
      (node (ref "U4") (pin "14") (pinfunction "~{RTS}_14") (pintype "bidirectional"))
    )
    (net (code "67") (name "SENSE") (class "Default")
      (node (ref "R14") (pin "2") (pinfunction "2_2") (pintype "passive"))
      (node (ref "U1") (pin "16") (pinfunction "BRUV_16") (pintype "bidirectional"))
      (node (ref "U1") (pin "20") (pinfunction "BRW_20") (pintype "bidirectional"))
      (node (ref "U9") (pin "3") (pinfunction "+IN_3") (pintype "input"))
    )
    (net (code "68") (name "SENSE_U") (class "Default")
      (node (ref "R32") (pin "1") (pinfunction "1_1") (pintype "passive"))
      (node (ref "U1") (pin "15") (pinfunction "U_15") (pintype "bidirectional"))
      (node (ref "U7") (pin "8") (pinfunction "IN+_8") (pintype "input"))
    )
    (net (code "69") (name "SENSE_V") (class "Default")
      (node (ref "R33") (pin "1") (pinfunction "1_1") (pintype "passive"))
      (node (ref "U1") (pin "17") (pinfunction "V_17") (pintype "bidirectional"))
      (node (ref "U11") (pin "8") (pinfunction "IN+_8") (pintype "input"))
    )
    (net (code "70") (name "SENSE_W") (class "Default")
      (node (ref "R34") (pin "1") (pinfunction "1_1") (pintype "passive"))
      (node (ref "U1") (pin "1") (pinfunction "W_1") (pintype "bidirectional"))
      (node (ref "U10") (pin "8") (pinfunction "IN+_8") (pintype "input"))
    )
    (net (code "71") (name "U") (class "Default")
      (node (ref "P1") (pin "3") (pinfunction "3_3") (pintype "passive"))
      (node (ref "R32") (pin "2") (pinfunction "2_2") (pintype "passive"))
      (node (ref "TP13") (pin "1") (pinfunction "1_1") (pintype "bidirectional"))
      (node (ref "U7") (pin "1") (pinfunction "IN-_1") (pintype "input"))
    )
    (net (code "72") (name "V") (class "Default")
      (node (ref "P1") (pin "2") (pinfunction "2_2") (pintype "passive"))
      (node (ref "R33") (pin "2") (pinfunction "2_2") (pintype "passive"))
      (node (ref "TP14") (pin "1") (pinfunction "1_1") (pintype "bidirectional"))
      (node (ref "U11") (pin "1") (pinfunction "IN-_1") (pintype "input"))
    )
    (net (code "73") (name "V_USB") (class "Default")
      (node (ref "C6") (pin "1") (pinfunction "1_1") (pintype "passive"))
      (node (ref "C7") (pin "+") (pinfunction "+_+") (pintype "passive"))
      (node (ref "J1") (pin "VBUS1") (pinfunction "VBUS_VBUS1") (pintype "bidirectional"))
      (node (ref "J1") (pin "VBUS2") (pinfunction "VBUS_VBUS2") (pintype "bidirectional"))
      (node (ref "Q1") (pin "6") (pinfunction "C_6") (pintype "passive"))
      (node (ref "Q3") (pin "3") (pinfunction "D_3") (pintype "bidirectional"))
      (node (ref "U5") (pin "5") (pinfunction "VCC_5") (pintype "bidirectional"))
    )
    (net (code "74") (name "W") (class "Default")
      (node (ref "P1") (pin "1") (pinfunction "1_1") (pintype "passive"))
      (node (ref "R34") (pin "2") (pinfunction "2_2") (pintype "passive"))
      (node (ref "TP15") (pin "1") (pinfunction "1_1") (pintype "bidirectional"))
      (node (ref "U10") (pin "1") (pinfunction "IN-_1") (pintype "input"))
    )
    (net (code "75") (name "unconnected-(U4-R232-Pad15)") (class "Default")
      (node (ref "U4") (pin "15") (pinfunction "R232_15") (pintype "bidirectional"))
    )
    (net (code "76") (name "unconnected-(U4-~{CTS}-Pad9)") (class "Default")
      (node (ref "U4") (pin "9") (pinfunction "~{CTS}_9") (pintype "bidirectional"))
    )
    (net (code "77") (name "unconnected-(U4-~{DCD}-Pad12)") (class "Default")
      (node (ref "U4") (pin "12") (pinfunction "~{DCD}_12") (pintype "bidirectional"))
    )
    (net (code "78") (name "unconnected-(U4-~{DSR}-Pad10)") (class "Default")
      (node (ref "U4") (pin "10") (pinfunction "~{DSR}_10") (pintype "bidirectional"))
    )
    (net (code "79") (name "unconnected-(U4-~{RI}-Pad11)") (class "Default")
      (node (ref "U4") (pin "11") (pinfunction "~{RI}_11") (pintype "bidirectional"))
    )
    (net (code "80") (name "unconnected-(U5-IO1-Pad1)") (class "Default")
      (node (ref "U5") (pin "1") (pinfunction "IO1_1") (pintype "bidirectional"))
    )
    (net (code "81") (name "unconnected-(U5-IO2-Pad3)") (class "Default")
      (node (ref "U5") (pin "3") (pinfunction "IO2_3") (pintype "bidirectional"))
    )
  )
)
